# MotorDriverDRV8313_1.net
KiCad netlist of a schematic drawn in Altium Designer
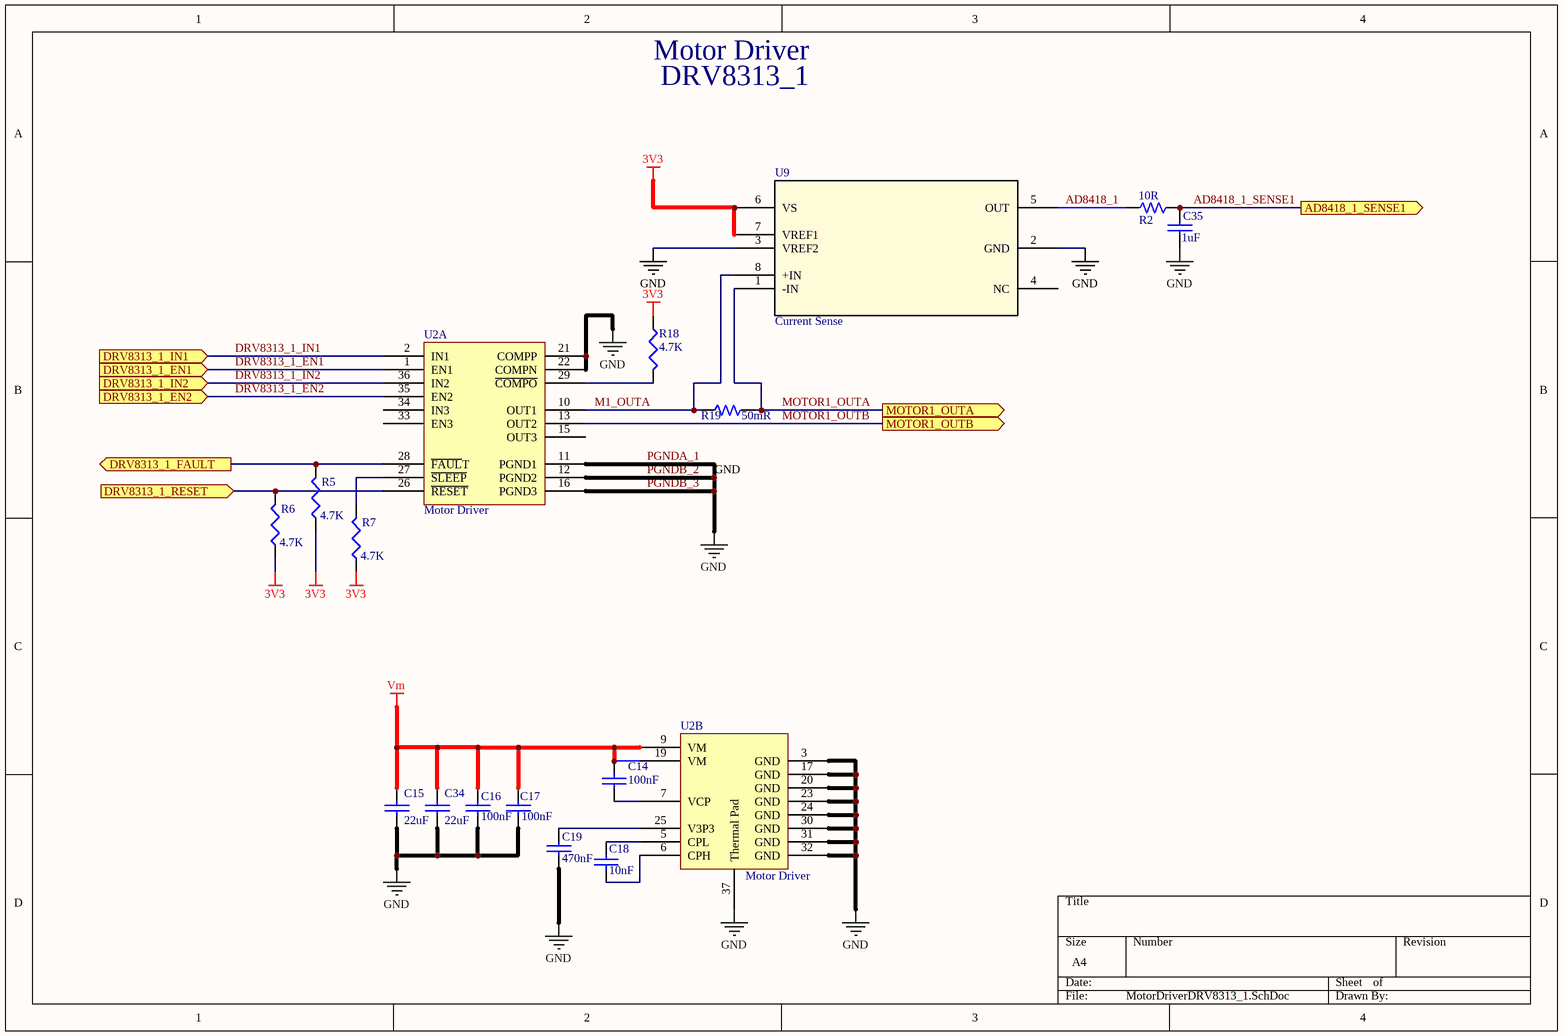
[diagram p0: MotorDriverDRV8313_1.SchDoc]

(export (version "E")
  (design (tool "Eeschema 10.0.6"))
  (components
    (comp (ref "C14")
      (value "100nF")
      (footprint "CAP0402")
      (description "Capacitor")
      (fields
        (field (name "MANUFACTURER") "TDK Corporation")
        (field (name "MANUFACTURER PART NUMBER") "CGA2B3X7R1V104K050BB")
      )
      (libsource (lib "BPL-ShematicLibrary") (part "Capacitor"))
    )
    (comp (ref "C15")
      (value "22uF")
      (footprint "CAP0805")
      (description "Capacitor")
      (fields
        (field (name "MANUFACTURER") "TDK Corporation")
        (field (name "MANUFACTURER PART NUMBER") "C2012JB1V226M125AC")
      )
      (libsource (lib "BPL-ShematicLibrary") (part "Capacitor"))
    )
    (comp (ref "C16")
      (value "100nF")
      (footprint "CAP0402")
      (description "Capacitor")
      (fields
        (field (name "MANUFACTURER") "TDK Corporation")
        (field (name "MANUFACTURER PART NUMBER") "CGA2B3X7R1V104K050BB")
      )
      (libsource (lib "BPL-ShematicLibrary") (part "Capacitor"))
    )
    (comp (ref "C17")
      (value "100nF")
      (footprint "CAP0402")
      (description "Capacitor")
      (fields
        (field (name "MANUFACTURER") "TDK Corporation")
        (field (name "MANUFACTURER PART NUMBER") "CGA2B3X7R1V104K050BB")
      )
      (libsource (lib "BPL-ShematicLibrary") (part "Capacitor"))
    )
    (comp (ref "C18")
      (value "10nF")
      (footprint "CAP0402")
      (description "Capacitor")
      (fields
        (field (name "MANUFACTURER") "TDK Corporation")
        (field (name "MANUFACTURER PART NUMBER") "C1005X7R1V103K050BB")
      )
      (libsource (lib "BPL-ShematicLibrary") (part "Capacitor"))
    )
    (comp (ref "C19")
      (value "470nF")
      (footprint "CAP0402")
      (description "Capacitor")
      (fields
        (field (name "MANUFACTURER") "Murata Electronics North America")
        (field (name "MANUFACTURER PART NUMBER") "GRM155R61A474KE15D")
      )
      (libsource (lib "BPL-ShematicLibrary") (part "Capacitor"))
    )
    (comp (ref "C34")
      (value "22uF")
      (footprint "CAP0805")
      (description "Capacitor")
      (fields
        (field (name "MANUFACTURER") "TDK Corporation")
        (field (name "MANUFACTURER PART NUMBER") "C2012JB1V226M125AC")
      )
      (libsource (lib "BPL-ShematicLibrary") (part "Capacitor"))
    )
    (comp (ref "C35")
      (value "1uF")
      (footprint "CAP0402")
      (description "Capacitor")
      (fields
        (field (name "MANUFACTURER") "TDK Corporation")
        (field (name "MANUFACTURER PART NUMBER") "C1005X5R1V105K050BC")
      )
      (libsource (lib "BPL-ShematicLibrary") (part "Capacitor"))
    )
    (comp (ref "R2")
      (value "Resistor")
      (footprint "RES0402")
      (fields (field (name "RESISTANCE") "10R") (field (name "TOLERANCE") "1%"))
      (libsource (lib "") (part "Resistor_1"))
    )
    (comp (ref "R5")
      (value "4.7K")
      (footprint "RES0402")
      (description "Resistor")
      (fields
        (field (name "MANUFACTURER") "Yageo")
        (field (name "MANUFACTURER PART NUMBER") "RC0402JR-074K7L")
      )
      (libsource (lib "BPL-ShematicLibrary") (part "Resistor"))
    )
    (comp (ref "R6")
      (value "4.7K")
      (footprint "RES0402")
      (description "Resistor")
      (fields
        (field (name "MANUFACTURER") "Yageo")
        (field (name "MANUFACTURER PART NUMBER") "RC0402JR-074K7L")
      )
      (libsource (lib "BPL-ShematicLibrary") (part "Resistor"))
    )
    (comp (ref "R7")
      (value "4.7K")
      (footprint "RES0402")
      (description "Resistor")
      (fields
        (field (name "MANUFACTURER") "Yageo")
        (field (name "MANUFACTURER PART NUMBER") "RC0402JR-074K7L")
      )
      (libsource (lib "BPL-ShematicLibrary") (part "Resistor"))
    )
    (comp (ref "R18")
      (value "4.7K")
      (footprint "RES0402")
      (description "Resistor")
      (fields
        (field (name "MANUFACTURER") "Yageo")
        (field (name "MANUFACTURER PART NUMBER") "RC0402JR-074K7L")
      )
      (libsource (lib "BPL-ShematicLibrary") (part "Resistor"))
    )
    (comp (ref "R19")
      (value "Resistor")
      (footprint "RES0805")
      (fields (field (name "RESISTANCE") "50mR") (field (name "TOLERANCE") "1%"))
      (libsource (lib "") (part "Resistor_1"))
    )
    (comp (ref "U2")
      (value "Motor Driver")
      (footprint "DRV8313RHHR")
      (description "2.5A 3-phase BLDC controller")
      (fields
        (field (name "MANUFACTURER") "Texas Instruments")
        (field (name "MANUFACTURER PART NUMBER") "DRV8313RHHR")
      )
      (libsource (lib "BPL-ShematicLibrary") (part "DRV8313RHHR"))
    )
    (comp (ref "U9")
      (value "Current Sense")
      (footprint "AD8418BRMZ")
      (description "Imported")
      (fields
        (field (name "MANUFACTURER") "Analog Devices Inc")
        (field (name "MANUFACTURER PART NUMBER") "AD8418BRMZ")
      )
      (libsource (lib "BPL-ShematicLibrary") (part "AD8418BRMZ"))
    )
  )
  (nets
    (net (code "1") (name "/AD8418_1") (class "Default")
      (node (ref "R2") (pin "1") (pinfunction "1_1") (pintype "passive"))
      (node (ref "U9") (pin "5") (pinfunction "OUT_5") (pintype "passive"))
    )
    (net (code "2") (name "/AD8418_1_SENSE1") (class "Default")
      (node (ref "C35") (pin "1") (pinfunction "1_1") (pintype "passive"))
      (node (ref "R2") (pin "2") (pinfunction "2_2") (pintype "passive"))
    )
    (net (code "3") (name "/DRV8313_1_EN1") (class "Default")
      (node (ref "U2") (pin "1") (pinfunction "EN1_1") (pintype "passive"))
    )
    (net (code "4") (name "/DRV8313_1_EN2") (class "Default")
      (node (ref "U2") (pin "35") (pinfunction "EN2_35") (pintype "passive"))
    )
    (net (code "5") (name "/DRV8313_1_FAULT") (class "Default")
      (node (ref "R5") (pin "2") (pinfunction "2_2") (pintype "passive"))
      (node (ref "U2") (pin "28") (pinfunction "~{FAUL}T_28") (pintype "passive"))
    )
    (net (code "6") (name "/DRV8313_1_IN1") (class "Default")
      (node (ref "U2") (pin "2") (pinfunction "IN1_2") (pintype "passive"))
    )
    (net (code "7") (name "/DRV8313_1_IN2") (class "Default")
      (node (ref "U2") (pin "36") (pinfunction "IN2_36") (pintype "passive"))
    )
    (net (code "8") (name "/DRV8313_1_RESET") (class "Default")
      (node (ref "R6") (pin "2") (pinfunction "2_2") (pintype "passive"))
      (node (ref "U2") (pin "26") (pinfunction "~{RESET}_26") (pintype "passive"))
    )
    (net (code "9") (name "/M1_OUTA") (class "Default")
      (node (ref "R19") (pin "1") (pinfunction "1_1") (pintype "passive"))
      (node (ref "U2") (pin "10") (pinfunction "OUT1_10") (pintype "passive"))
      (node (ref "U9") (pin "8") (pinfunction "+IN_8") (pintype "passive"))
    )
    (net (code "10") (name "/MOTOR1_OUTA") (class "Default")
      (node (ref "R19") (pin "2") (pinfunction "2_2") (pintype "passive"))
      (node (ref "U9") (pin "1") (pinfunction "-IN_1") (pintype "passive"))
    )
    (net (code "11") (name "/MOTOR1_OUTB") (class "Default")
      (node (ref "U2") (pin "13") (pinfunction "OUT2_13") (pintype "passive"))
    )
    (net (code "12") (name "3V3") (class "Default")
      (node (ref "R18") (pin "1") (pinfunction "1_1") (pintype "passive"))
      (node (ref "R5") (pin "1") (pinfunction "1_1") (pintype "passive"))
      (node (ref "R6") (pin "1") (pinfunction "1_1") (pintype "passive"))
      (node (ref "R7") (pin "1") (pinfunction "1_1") (pintype "passive"))
      (node (ref "U9") (pin "6") (pinfunction "VS_6") (pintype "passive"))
      (node (ref "U9") (pin "7") (pinfunction "VREF1_7") (pintype "passive"))
    )
    (net (code "13") (name "GND") (class "Default")
      (node (ref "C15") (pin "2") (pinfunction "2_2") (pintype "passive"))
      (node (ref "C16") (pin "2") (pinfunction "2_2") (pintype "passive"))
      (node (ref "C17") (pin "2") (pinfunction "2_2") (pintype "passive"))
      (node (ref "C19") (pin "2") (pinfunction "2_2") (pintype "passive"))
      (node (ref "C34") (pin "2") (pinfunction "2_2") (pintype "passive"))
      (node (ref "C35") (pin "2") (pinfunction "2_2") (pintype "passive"))
      (node (ref "U2") (pin "11") (pinfunction "PGND1_11") (pintype "passive"))
      (node (ref "U2") (pin "12") (pinfunction "PGND2_12") (pintype "passive"))
      (node (ref "U2") (pin "16") (pinfunction "PGND3_16") (pintype "passive"))
      (node (ref "U2") (pin "17") (pinfunction "GND_17") (pintype "passive"))
      (node (ref "U2") (pin "20") (pinfunction "GND_20") (pintype "passive"))
      (node (ref "U2") (pin "21") (pinfunction "COMPP_21") (pintype "passive"))
      (node (ref "U2") (pin "22") (pinfunction "COMPN_22") (pintype "passive"))
      (node (ref "U2") (pin "23") (pinfunction "GND_23") (pintype "passive"))
      (node (ref "U2") (pin "24") (pinfunction "GND_24") (pintype "passive"))
      (node (ref "U2") (pin "3") (pinfunction "GND_3") (pintype "passive"))
      (node (ref "U2") (pin "30") (pinfunction "GND_30") (pintype "passive"))
      (node (ref "U2") (pin "31") (pinfunction "GND_31") (pintype "passive"))
      (node (ref "U2") (pin "32") (pinfunction "GND_32") (pintype "passive"))
      (node (ref "U2") (pin "37") (pinfunction "Thermal_Pad_37") (pintype "passive"))
      (node (ref "U9") (pin "2") (pinfunction "GND_2") (pintype "passive"))
      (node (ref "U9") (pin "3") (pinfunction "VREF2_3") (pintype "passive"))
    )
    (net (code "14") (name "Net-(U2A-~{COMPO})") (class "Default")
      (node (ref "R18") (pin "2") (pinfunction "2_2") (pintype "passive"))
      (node (ref "U2") (pin "29") (pinfunction "~{COMPO}_29") (pintype "passive"))
    )
    (net (code "15") (name "Net-(U2A-~{SLEEP})") (class "Default")
      (node (ref "R7") (pin "2") (pinfunction "2_2") (pintype "passive"))
      (node (ref "U2") (pin "27") (pinfunction "~{SLEEP}_27") (pintype "passive"))
    )
    (net (code "16") (name "Net-(U2B-CPH)") (class "Default")
      (node (ref "C18") (pin "2") (pinfunction "2_2") (pintype "passive"))
      (node (ref "U2") (pin "6") (pinfunction "CPH_6") (pintype "passive"))
    )
    (net (code "17") (name "Net-(U2B-CPL)") (class "Default")
      (node (ref "C18") (pin "1") (pinfunction "1_1") (pintype "passive"))
      (node (ref "U2") (pin "5") (pinfunction "CPL_5") (pintype "passive"))
    )
    (net (code "18") (name "Net-(U2B-V3P3)") (class "Default")
      (node (ref "C19") (pin "1") (pinfunction "1_1") (pintype "passive"))
      (node (ref "U2") (pin "25") (pinfunction "V3P3_25") (pintype "passive"))
    )
    (net (code "19") (name "Net-(U2B-VCP)") (class "Default")
      (node (ref "C14") (pin "2") (pinfunction "2_2") (pintype "passive"))
      (node (ref "U2") (pin "7") (pinfunction "VCP_7") (pintype "passive"))
    )
    (net (code "20") (name "Vm") (class "Default")
      (node (ref "C14") (pin "1") (pinfunction "1_1") (pintype "passive"))
      (node (ref "C15") (pin "1") (pinfunction "1_1") (pintype "passive"))
      (node (ref "C16") (pin "1") (pinfunction "1_1") (pintype "passive"))
      (node (ref "C17") (pin "1") (pinfunction "1_1") (pintype "passive"))
      (node (ref "C34") (pin "1") (pinfunction "1_1") (pintype "passive"))
      (node (ref "U2") (pin "19") (pinfunction "VM_19") (pintype "passive"))
      (node (ref "U2") (pin "9") (pinfunction "VM_9") (pintype "passive"))
    )
    (net (code "21") (name "unconnected-(U2A-EN3-Pad33)") (class "Default")
      (node (ref "U2") (pin "33") (pinfunction "EN3_33") (pintype "passive"))
    )
    (net (code "22") (name "unconnected-(U2A-IN3-Pad34)") (class "Default")
      (node (ref "U2") (pin "34") (pinfunction "IN3_34") (pintype "passive"))
    )
    (net (code "23") (name "unconnected-(U2A-OUT3-Pad15)") (class "Default")
      (node (ref "U2") (pin "15") (pinfunction "OUT3_15") (pintype "passive"))
    )
    (net (code "24") (name "unconnected-(U9-NC-Pad4)") (class "Default")
      (node (ref "U9") (pin "4") (pinfunction "NC_4") (pintype "passive"))
    )
  )
)
